# NOT-A.net
KiCad netlist of a schematic drawn in EAGLE
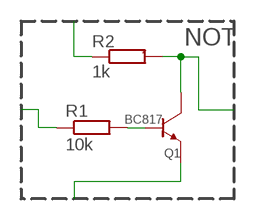
[diagram p0: schematic, sheet 1]

(export (version "E")
  (design (tool "Eeschema 10.0.6"))
  (components
    (comp (ref "Q1")
      (value "BC817")
      (footprint "eagle-import:SOT23")
      (libsource (lib "eagle-import") (part "TRANSISTOR-NPN-GENERIC-SOT23-BECDEFAULT"))
    )
    (comp (ref "R1")
      (value "10k")
      (footprint "eagle-import:R0603")
      (libsource (lib "eagle-import") (part "R-EU_R0603"))
    )
    (comp (ref "R2")
      (value "1k")
      (footprint "eagle-import:R0603-MARK")
      (libsource (lib "eagle-import") (part "R-EU-MARKEDR0603"))
    )
  )
  (nets
    (net (code "1") (name "Net-(Q1-BASE)") (class "Default")
      (node (ref "Q1") (pin "P$1") (pinfunction "BASE_P$1") (pintype "bidirectional"))
      (node (ref "R1") (pin "2") (pinfunction "2_2") (pintype "passive"))
    )
    (net (code "2") (name "Net-(Q1-COLLECTOR)") (class "Default")
      (node (ref "Q1") (pin "P$3") (pinfunction "COLLECTOR_P$3") (pintype "bidirectional"))
      (node (ref "R2") (pin "2") (pinfunction "2_2") (pintype "passive"))
    )
    (net (code "3") (name "unconnected-(Q1-EMITTER-PadP$2)") (class "Default")
      (node (ref "Q1") (pin "P$2") (pinfunction "EMITTER_P$2") (pintype "bidirectional"))
    )
    (net (code "4") (name "unconnected-(R1-Pad1)") (class "Default")
      (node (ref "R1") (pin "1") (pinfunction "1_1") (pintype "passive"))
    )
    (net (code "5") (name "unconnected-(R2-Pad1)") (class "Default")
      (node (ref "R2") (pin "1") (pinfunction "1_1") (pintype "passive"))
    )
  )
)
